# schematic.net
KiCad netlist of a schematic drawn in EAGLE
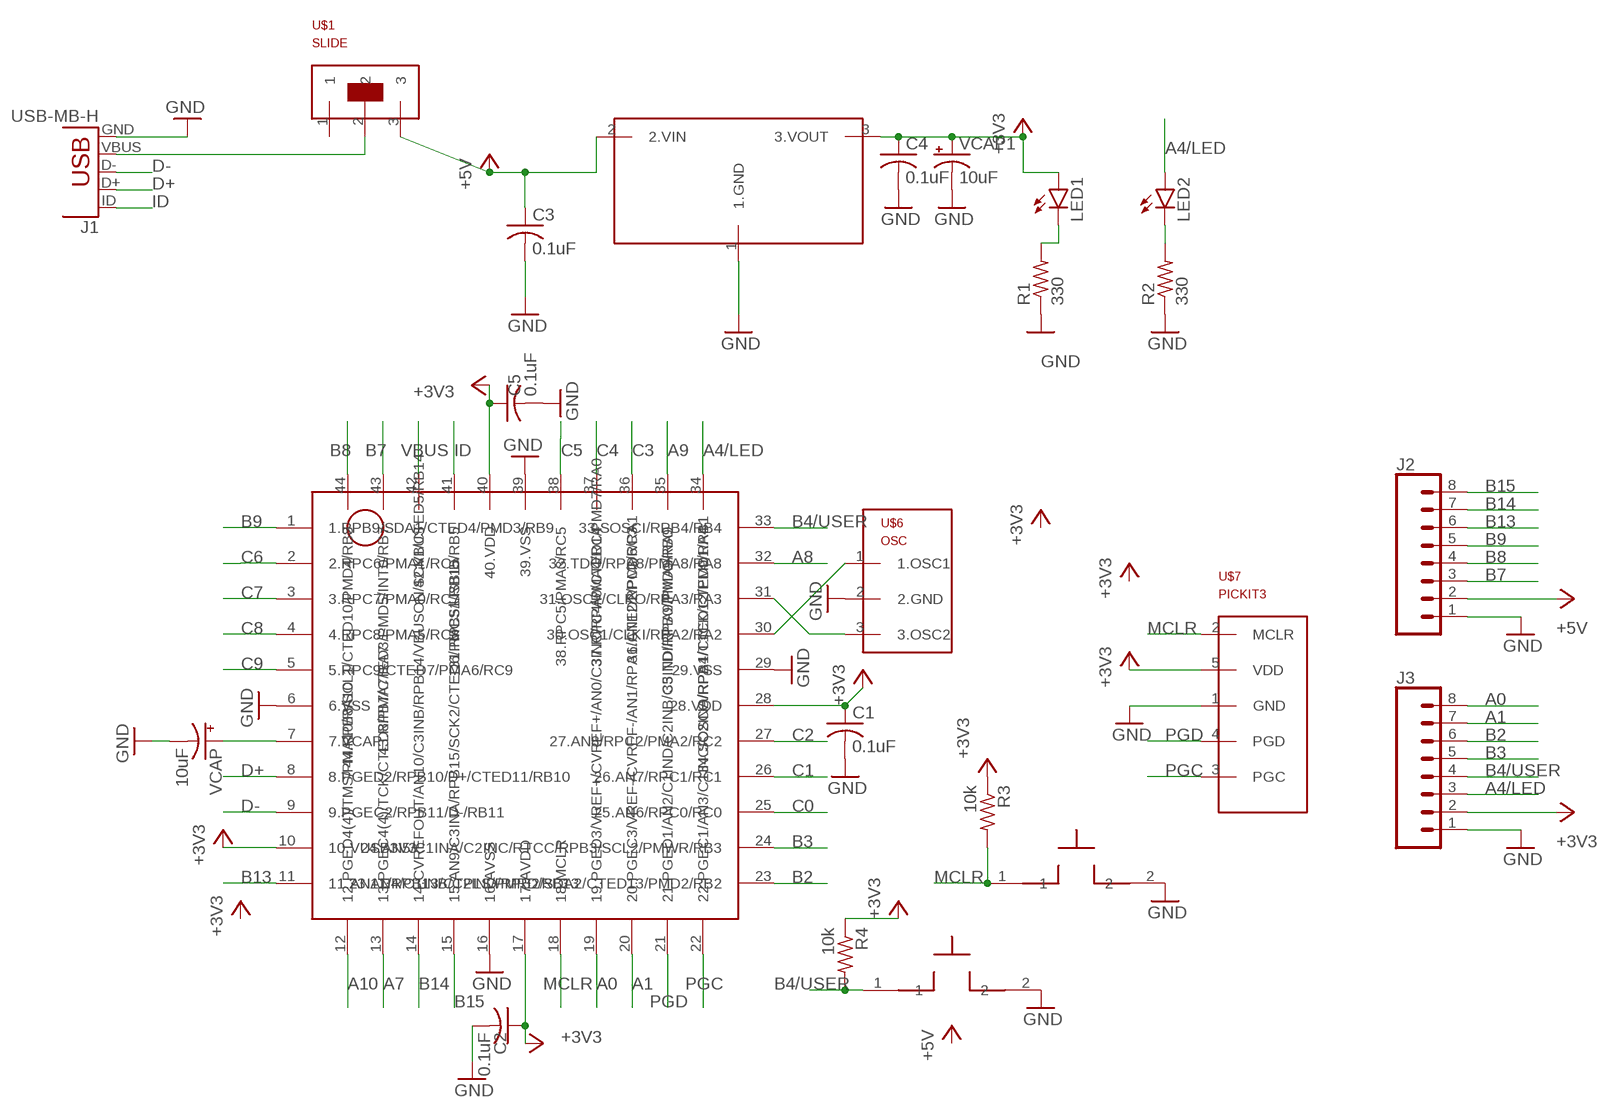
[diagram p0: schematic, sheet 1]

(export (version "E")
  (design (tool "Eeschema 10.0.6"))
  (components
    (comp (ref "C1")
      (value "0.1uF")
      (footprint "eagle-import:C025-025X050")
      (libsource (lib "eagle-import") (part "C-US025-025X050"))
    )
    (comp (ref "C2")
      (value "0.1uF")
      (footprint "eagle-import:C025-025X050")
      (libsource (lib "eagle-import") (part "C-US025-025X050"))
    )
    (comp (ref "C3")
      (value "0.1uF")
      (footprint "eagle-import:C025-025X050")
      (libsource (lib "eagle-import") (part "C-US025-025X050"))
    )
    (comp (ref "C4")
      (value "0.1uF")
      (footprint "eagle-import:C025-025X050")
      (libsource (lib "eagle-import") (part "C-US025-025X050"))
    )
    (comp (ref "C5")
      (value "0.1uF")
      (footprint "eagle-import:C025-025X050")
      (libsource (lib "eagle-import") (part "C-US025-025X050"))
    )
    (comp (ref "J1")
      (value "USB-MB-H")
      (footprint "eagle-import:USB-MB-H")
      (libsource (lib "eagle-import") (part "USB-MB-H"))
    )
    (comp (ref "J2")
      (value "CONN_08\"")
      (footprint "eagle-import:1X08")
      (libsource (lib "eagle-import") (part "CONN_08{dblquote}"))
    )
    (comp (ref "J3")
      (value "CONN_08\"")
      (footprint "eagle-import:1X08")
      (libsource (lib "eagle-import") (part "CONN_08{dblquote}"))
    )
    (comp (ref "LED1")
      (value "LED3MM")
      (footprint "eagle-import:LED3MM")
      (libsource (lib "eagle-import") (part "LED3MM"))
    )
    (comp (ref "LED2")
      (value "LED3MM")
      (footprint "eagle-import:LED3MM")
      (libsource (lib "eagle-import") (part "LED3MM"))
    )
    (comp (ref "R1")
      (value "330")
      (footprint "eagle-import:0207_10")
      (libsource (lib "eagle-import") (part "R-US_0207/10"))
    )
    (comp (ref "R2")
      (value "330")
      (footprint "eagle-import:0207_10")
      (libsource (lib "eagle-import") (part "R-US_0207/10"))
    )
    (comp (ref "R3")
      (value "10k")
      (footprint "eagle-import:0207_10")
      (libsource (lib "eagle-import") (part "R-US_0207/10"))
    )
    (comp (ref "R4")
      (value "10k")
      (footprint "eagle-import:0207_10")
      (libsource (lib "eagle-import") (part "R-US_0207/10"))
    )
    (comp (ref "RESET")
      (value "BUTTON")
      (footprint "eagle-import:BUTTON")
      (libsource (lib "eagle-import") (part "BUTTON"))
    )
    (comp (ref "U$1")
      (value "SLIDE")
      (footprint "eagle-import:SWITCH")
      (libsource (lib "eagle-import") (part "SLIDE"))
    )
    (comp (ref "U$2")
      (value "PIC32MX")
      (footprint "eagle-import:TQFP44")
      (libsource (lib "eagle-import") (part "PIC32MX"))
    )
    (comp (ref "U$3")
      (value "TO92VOLTREG")
      (footprint "eagle-import:TO92")
      (libsource (lib "eagle-import") (part "TO92VOLTREG"))
    )
    (comp (ref "U$6")
      (value "OSC")
      (footprint "eagle-import:OSC")
      (libsource (lib "eagle-import") (part "OSC"))
    )
    (comp (ref "U$7")
      (value "PICKIT3")
      (footprint "eagle-import:1X05")
      (libsource (lib "eagle-import") (part "PICKIT3"))
    )
    (comp (ref "USER")
      (value "BUTTON")
      (footprint "eagle-import:BUTTON")
      (libsource (lib "eagle-import") (part "BUTTON"))
    )
    (comp (ref "VCAP")
      (value "10uF")
      (footprint "eagle-import:B45181B")
      (libsource (lib "eagle-import") (part "CPOL-USB45181B"))
    )
    (comp (ref "VCAP1")
      (value "10uF")
      (footprint "eagle-import:B45181B")
      (libsource (lib "eagle-import") (part "CPOL-USB45181B"))
    )
  )
  (nets
    (net (code "1") (name "+3V3") (class "Default")
      (node (ref "C1") (pin "1") (pinfunction "1_1") (pintype "passive"))
      (node (ref "C2") (pin "1") (pinfunction "1_1") (pintype "passive"))
      (node (ref "C4") (pin "1") (pinfunction "1_1") (pintype "passive"))
      (node (ref "C5") (pin "1") (pinfunction "1_1") (pintype "passive"))
      (node (ref "J3") (pin "2") (pinfunction "2_2") (pintype "passive"))
      (node (ref "LED1") (pin "A") (pinfunction "A_A") (pintype "passive"))
      (node (ref "R3") (pin "1") (pinfunction "1_1") (pintype "passive"))
      (node (ref "R4") (pin "1") (pinfunction "1_1") (pintype "passive"))
      (node (ref "U$2") (pin "10") (pinfunction "10.VUSB3V3_10") (pintype "bidirectional"))
      (node (ref "U$2") (pin "17") (pinfunction "17.AVDD_17") (pintype "bidirectional"))
      (node (ref "U$2") (pin "28") (pinfunction "28.VDD_28") (pintype "bidirectional"))
      (node (ref "U$2") (pin "40") (pinfunction "40.VDD_40") (pintype "bidirectional"))
      (node (ref "U$3") (pin "3") (pinfunction "3.VOUT_3") (pintype "bidirectional"))
      (node (ref "U$7") (pin "5") (pinfunction "VDD_5") (pintype "bidirectional"))
      (node (ref "VCAP1") (pin "+") (pinfunction "+_+") (pintype "passive"))
    )
    (net (code "2") (name "+5V") (class "Default")
      (node (ref "C3") (pin "1") (pinfunction "1_1") (pintype "passive"))
      (node (ref "J2") (pin "2") (pinfunction "2_2") (pintype "passive"))
      (node (ref "U$1") (pin "3") (pinfunction "3_3") (pintype "bidirectional"))
      (node (ref "U$3") (pin "2") (pinfunction "2.VIN_2") (pintype "bidirectional"))
    )
    (net (code "3") (name "/A0") (class "Default")
      (node (ref "J3") (pin "8") (pinfunction "8_8") (pintype "passive"))
      (node (ref "U$2") (pin "19") (pinfunction "19.PGED3/VREF+/CVREF+/AN0/C3INC/RPA0/CTED1/PMD7/RA0_19") (pintype "bidirectional"))
    )
    (net (code "4") (name "/A1") (class "Default")
      (node (ref "J3") (pin "7") (pinfunction "7_7") (pintype "passive"))
      (node (ref "U$2") (pin "20") (pinfunction "20.PGEC3/VREF-/CVREF-/AN1/RPA1/CTED2/PMD6/RA1_20") (pintype "bidirectional"))
    )
    (net (code "5") (name "/A4{slash}LED") (class "Default")
      (node (ref "J3") (pin "3") (pinfunction "3_3") (pintype "passive"))
      (node (ref "LED2") (pin "A") (pinfunction "A_A") (pintype "passive"))
      (node (ref "U$2") (pin "34") (pinfunction "34.SOSCO/RPA4/T1CK/CTED9/RA4_34") (pintype "bidirectional"))
    )
    (net (code "6") (name "/A7") (class "Default")
      (node (ref "U$2") (pin "13") (pinfunction "13.PGEC4(4)/TCK/CTED8/PMA7/RA7_13") (pintype "bidirectional"))
    )
    (net (code "7") (name "/A8") (class "Default")
      (node (ref "U$2") (pin "32") (pinfunction "32.TDO/RPA8/PMA8/RA8_32") (pintype "bidirectional"))
    )
    (net (code "8") (name "/A9") (class "Default")
      (node (ref "U$2") (pin "35") (pinfunction "35.TDI/RPA9/PMA9/RA9_35") (pintype "bidirectional"))
    )
    (net (code "9") (name "/A10") (class "Default")
      (node (ref "U$2") (pin "12") (pinfunction "12.PGED4(4)/TMS/PMA10/RA10_12") (pintype "bidirectional"))
    )
    (net (code "10") (name "/B2") (class "Default")
      (node (ref "J3") (pin "6") (pinfunction "6_6") (pintype "passive"))
      (node (ref "U$2") (pin "23") (pinfunction "23.AN4/C1INB/C2IND/RPB2/SDA2/CTED13/PMD2/RB2_23") (pintype "bidirectional"))
    )
    (net (code "11") (name "/B3") (class "Default")
      (node (ref "J3") (pin "5") (pinfunction "5_5") (pintype "passive"))
      (node (ref "U$2") (pin "24") (pinfunction "24.AN5/C1INA/C2INC/RTCC/RPB3/SCL2/PMWR/RB3_24") (pintype "bidirectional"))
    )
    (net (code "12") (name "/B4{slash}USER") (class "Default")
      (node (ref "J3") (pin "4") (pinfunction "4_4") (pintype "passive"))
      (node (ref "R4") (pin "2") (pinfunction "2_2") (pintype "passive"))
      (node (ref "U$2") (pin "33") (pinfunction "33.SOSCI/RPB4/RB4_33") (pintype "bidirectional"))
      (node (ref "USER") (pin "1") (pinfunction "1_1") (pintype "bidirectional"))
    )
    (net (code "13") (name "/B7") (class "Default")
      (node (ref "J2") (pin "3") (pinfunction "3_3") (pintype "passive"))
      (node (ref "U$2") (pin "43") (pinfunction "43.RPB7/CTED3/PMD5/INT0/RB7_43") (pintype "bidirectional"))
    )
    (net (code "14") (name "/B8") (class "Default")
      (node (ref "J2") (pin "4") (pinfunction "4_4") (pintype "passive"))
      (node (ref "U$2") (pin "44") (pinfunction "44.RPB8/SCL1/CTED10/PMD4/RB8_44") (pintype "bidirectional"))
    )
    (net (code "15") (name "/B9") (class "Default")
      (node (ref "J2") (pin "5") (pinfunction "5_5") (pintype "passive"))
      (node (ref "U$2") (pin "1") (pinfunction "1.RPB9/SDA1/CTED4/PMD3/RB9_1") (pintype "bidirectional"))
    )
    (net (code "16") (name "/B13") (class "Default")
      (node (ref "J2") (pin "6") (pinfunction "6_6") (pintype "passive"))
      (node (ref "U$2") (pin "11") (pinfunction "11.AN11/RPB13/CTPLS/PMRD/RB13_11") (pintype "bidirectional"))
    )
    (net (code "17") (name "/B14") (class "Default")
      (node (ref "J2") (pin "7") (pinfunction "7_7") (pintype "passive"))
      (node (ref "U$2") (pin "14") (pinfunction "14.CVREFOUT/AN10/C3INB/RPB14/VBUSON/SCK1/CTED5/RB14_14") (pintype "bidirectional"))
    )
    (net (code "18") (name "/B15") (class "Default")
      (node (ref "J2") (pin "8") (pinfunction "8_8") (pintype "passive"))
      (node (ref "U$2") (pin "15") (pinfunction "15.AN9/C3INA/RPB15/SCK2/CTED6/PMCS1/RB15_15") (pintype "bidirectional"))
    )
    (net (code "19") (name "/C0") (class "Default")
      (node (ref "U$2") (pin "25") (pinfunction "25.AN6/RPC0/RC0_25") (pintype "bidirectional"))
    )
    (net (code "20") (name "/C1") (class "Default")
      (node (ref "U$2") (pin "26") (pinfunction "26.AN7/RPC1/RC1_26") (pintype "bidirectional"))
    )
    (net (code "21") (name "/C2") (class "Default")
      (node (ref "U$2") (pin "27") (pinfunction "27.AN8/RPC2/PMA2/RC2_27") (pintype "bidirectional"))
    )
    (net (code "22") (name "/C3") (class "Default")
      (node (ref "U$2") (pin "36") (pinfunction "36.AN12/RPC3/RC3_36") (pintype "bidirectional"))
    )
    (net (code "23") (name "/C4") (class "Default")
      (node (ref "U$2") (pin "37") (pinfunction "37.RPC4/PMA4/RC4_37") (pintype "bidirectional"))
    )
    (net (code "24") (name "/C5") (class "Default")
      (node (ref "U$2") (pin "38") (pinfunction "38.RPC5/PMA3/RC5_38") (pintype "bidirectional"))
    )
    (net (code "25") (name "/C6") (class "Default")
      (node (ref "U$2") (pin "2") (pinfunction "2.RPC6/PMA1/RC6_2") (pintype "bidirectional"))
    )
    (net (code "26") (name "/C7") (class "Default")
      (node (ref "U$2") (pin "3") (pinfunction "3.RPC7/PMA0/RC7_3") (pintype "bidirectional"))
    )
    (net (code "27") (name "/C8") (class "Default")
      (node (ref "U$2") (pin "4") (pinfunction "4.RPC8/PMA5/RC8_4") (pintype "bidirectional"))
    )
    (net (code "28") (name "/C9") (class "Default")
      (node (ref "U$2") (pin "5") (pinfunction "5.RPC9/CTED7/PMA6/RC9_5") (pintype "bidirectional"))
    )
    (net (code "29") (name "/D+") (class "Default")
      (node (ref "J1") (pin "D+") (pinfunction "D+_D+") (pintype "bidirectional"))
      (node (ref "U$2") (pin "8") (pinfunction "8.PGED2/RPB10/D+/CTED11/RB10_8") (pintype "bidirectional"))
    )
    (net (code "30") (name "/D-") (class "Default")
      (node (ref "J1") (pin "D-") (pinfunction "D-_D-") (pintype "bidirectional"))
      (node (ref "U$2") (pin "9") (pinfunction "9.PGEC2/RPB11/D-/RB11_9") (pintype "bidirectional"))
    )
    (net (code "31") (name "/ID") (class "Default")
      (node (ref "J1") (pin "ID") (pinfunction "D+1_ID") (pintype "bidirectional"))
      (node (ref "U$2") (pin "41") (pinfunction "31.RPB5/USBID/RB5_41") (pintype "bidirectional"))
    )
    (net (code "32") (name "/MCLR") (class "Default")
      (node (ref "R3") (pin "2") (pinfunction "2_2") (pintype "passive"))
      (node (ref "RESET") (pin "1") (pinfunction "1_1") (pintype "bidirectional"))
      (node (ref "U$2") (pin "18") (pinfunction "18.MCLR_18") (pintype "bidirectional"))
      (node (ref "U$7") (pin "2") (pinfunction "MCLR_2") (pintype "bidirectional"))
    )
    (net (code "33") (name "/PGC") (class "Default")
      (node (ref "U$2") (pin "22") (pinfunction "22.PGEC1/AN3/C1INC/C2INA/RPB1/CTED12/PMD1/RB1_22") (pintype "bidirectional"))
      (node (ref "U$7") (pin "3") (pinfunction "PGC_3") (pintype "bidirectional"))
    )
    (net (code "34") (name "/PGD") (class "Default")
      (node (ref "U$2") (pin "21") (pinfunction "21.PGED1/AN2/C1IND/C2INB/C3IND/RPB0/PMD0/RB0_21") (pintype "bidirectional"))
      (node (ref "U$7") (pin "4") (pinfunction "PGD_4") (pintype "bidirectional"))
    )
    (net (code "35") (name "/VBUS") (class "Default")
      (node (ref "U$2") (pin "42") (pinfunction "42.VBUS_42") (pintype "bidirectional"))
    )
    (net (code "36") (name "GND") (class "Default")
      (node (ref "C1") (pin "2") (pinfunction "2_2") (pintype "passive"))
      (node (ref "C2") (pin "2") (pinfunction "2_2") (pintype "passive"))
      (node (ref "C3") (pin "2") (pinfunction "2_2") (pintype "passive"))
      (node (ref "C4") (pin "2") (pinfunction "2_2") (pintype "passive"))
      (node (ref "C5") (pin "2") (pinfunction "2_2") (pintype "passive"))
      (node (ref "J1") (pin "GND") (pinfunction "GND_GND") (pintype "bidirectional"))
      (node (ref "J2") (pin "1") (pinfunction "1_1") (pintype "passive"))
      (node (ref "J3") (pin "1") (pinfunction "1_1") (pintype "passive"))
      (node (ref "R1") (pin "1") (pinfunction "1_1") (pintype "passive"))
      (node (ref "R2") (pin "1") (pinfunction "1_1") (pintype "passive"))
      (node (ref "RESET") (pin "2") (pinfunction "2_2") (pintype "bidirectional"))
      (node (ref "U$2") (pin "16") (pinfunction "16.AVSS_16") (pintype "bidirectional"))
      (node (ref "U$2") (pin "29") (pinfunction "29.VSS_29") (pintype "bidirectional"))
      (node (ref "U$2") (pin "39") (pinfunction "39.VSS_39") (pintype "bidirectional"))
      (node (ref "U$2") (pin "6") (pinfunction "6.VSS_6") (pintype "bidirectional"))
      (node (ref "U$3") (pin "1") (pinfunction "1.GND_1") (pintype "bidirectional"))
      (node (ref "U$6") (pin "2") (pinfunction "2.GND_2") (pintype "bidirectional"))
      (node (ref "U$7") (pin "1") (pinfunction "GND_1") (pintype "bidirectional"))
      (node (ref "USER") (pin "2") (pinfunction "2_2") (pintype "bidirectional"))
      (node (ref "VCAP") (pin "-") (pinfunction "-_-") (pintype "passive"))
      (node (ref "VCAP1") (pin "-") (pinfunction "-_-") (pintype "passive"))
    )
    (net (code "37") (name "Net-(J1-PadVBUS)") (class "Default")
      (node (ref "J1") (pin "VBUS") (pinfunction "VBUS_VBUS") (pintype "bidirectional"))
      (node (ref "U$1") (pin "2") (pinfunction "2_2") (pintype "bidirectional"))
    )
    (net (code "38") (name "Net-(LED1-C)") (class "Default")
      (node (ref "LED1") (pin "K") (pinfunction "C_K") (pintype "passive"))
      (node (ref "R1") (pin "2") (pinfunction "2_2") (pintype "passive"))
    )
    (net (code "39") (name "Net-(LED2-C)") (class "Default")
      (node (ref "LED2") (pin "K") (pinfunction "C_K") (pintype "passive"))
      (node (ref "R2") (pin "2") (pinfunction "2_2") (pintype "passive"))
    )
    (net (code "40") (name "Net-(U$2-7.VCAP)") (class "Default")
      (node (ref "U$2") (pin "7") (pinfunction "7.VCAP_7") (pintype "bidirectional"))
      (node (ref "VCAP") (pin "+") (pinfunction "+_+") (pintype "passive"))
    )
    (net (code "41") (name "Net-(U$2-30.OSC1{slash}CLKI{slash}RPA2{slash}RA2)") (class "Default")
      (node (ref "U$2") (pin "30") (pinfunction "30.OSC1/CLKI/RPA2/RA2_30") (pintype "bidirectional"))
      (node (ref "U$6") (pin "1") (pinfunction "1.OSC1_1") (pintype "bidirectional"))
    )
    (net (code "42") (name "Net-(U$2-31.OSC2{slash}CLKO{slash}RPA3{slash}RA3)") (class "Default")
      (node (ref "U$2") (pin "31") (pinfunction "31.OSC2/CLKO/RPA3/RA3_31") (pintype "bidirectional"))
      (node (ref "U$6") (pin "3") (pinfunction "3.OSC2_3") (pintype "bidirectional"))
    )
    (net (code "43") (name "unconnected-(U$1-Pad1)") (class "Default")
      (node (ref "U$1") (pin "1") (pinfunction "1_1") (pintype "bidirectional"))
    )
  )
)
